# 453_mic.net
KiCad netlist of a schematic drawn in EAGLE
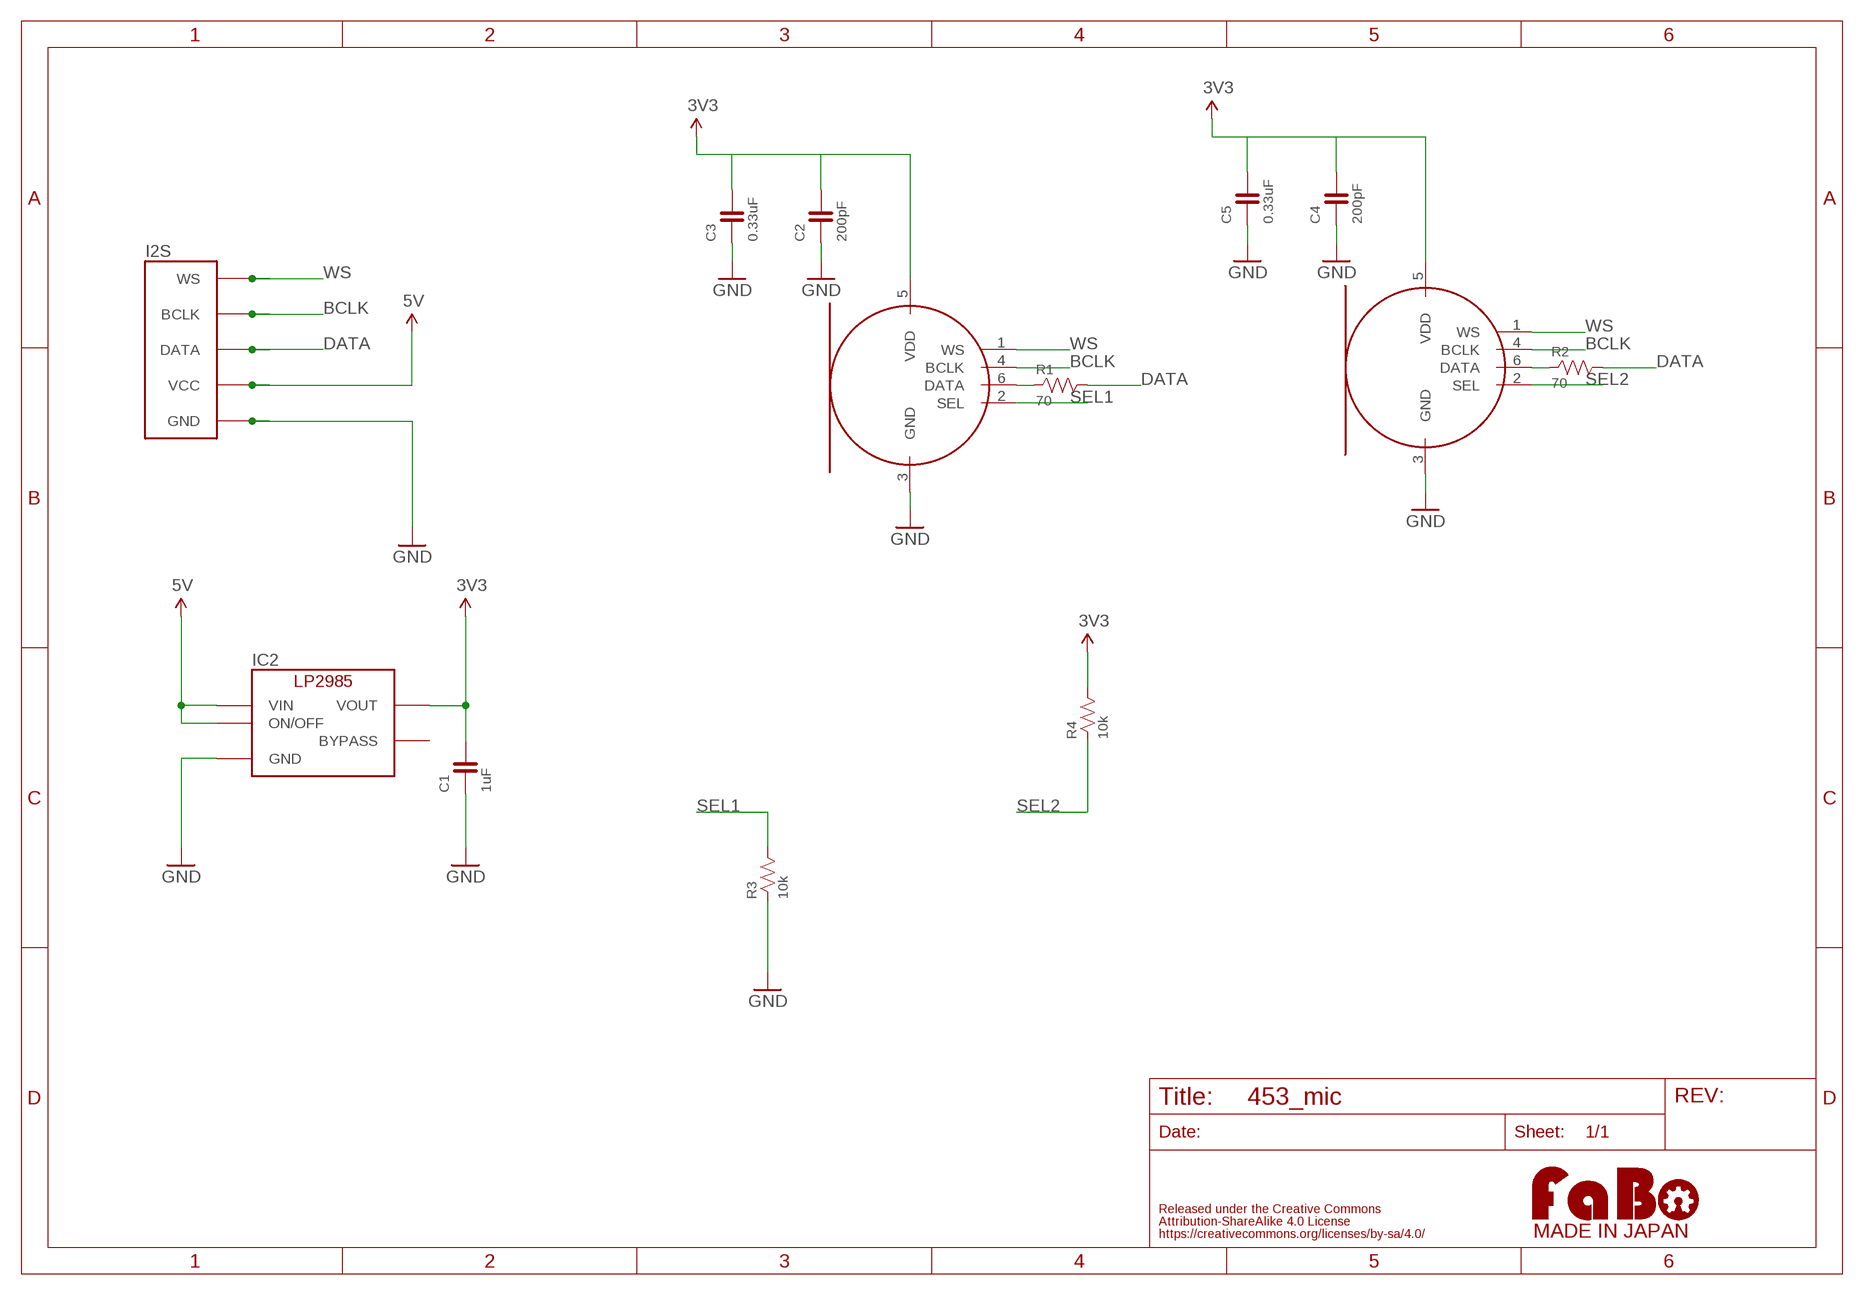
[diagram p0: schematic, sheet 1]

(export (version "E")
  (design (tool "Eeschema 10.0.6"))
  (components
    (comp (ref "C1")
      (value "1uF")
      (footprint "eagle-import:0603")
      (libsource (lib "eagle-import") (part "CAPACITOR-0603"))
    )
    (comp (ref "C2")
      (value "200pF")
      (footprint "eagle-import:0603")
      (libsource (lib "eagle-import") (part "CAPACITOR-0603"))
    )
    (comp (ref "C3")
      (value "0.33uF")
      (footprint "eagle-import:0603")
      (libsource (lib "eagle-import") (part "CAPACITOR-0603"))
    )
    (comp (ref "C4")
      (value "200pF")
      (footprint "eagle-import:0603")
      (libsource (lib "eagle-import") (part "CAPACITOR-0603"))
    )
    (comp (ref "C5")
      (value "0.33uF")
      (footprint "eagle-import:0603")
      (libsource (lib "eagle-import") (part "CAPACITOR-0603"))
    )
    (comp (ref "I2S")
      (value "FABO_BRICK_I2SLONG")
      (footprint "eagle-import:FABO_BRICK_I2S_S05B-PASK-2_LONG")
      (libsource (lib "eagle-import") (part "FABO_BRICK_I2SLONG"))
    )
    (comp (ref "IC2")
      (value "LP2985-33DBV")
      (footprint "eagle-import:SOT-23-5")
      (libsource (lib "eagle-import") (part "LP2985-33DBV"))
    )
    (comp (ref "MIC1")
      (value "KW-SPH0645")
      (footprint "eagle-import:KNOWLES-SPH0645")
      (libsource (lib "eagle-import") (part "KW-SPH0645"))
    )
    (comp (ref "MIC2")
      (value "KW-SPH0645")
      (footprint "eagle-import:KNOWLES-SPH0645")
      (libsource (lib "eagle-import") (part "KW-SPH0645"))
    )
    (comp (ref "R1")
      (value "70")
      (footprint "eagle-import:0603")
      (libsource (lib "eagle-import") (part "RESISTOR-0603"))
    )
    (comp (ref "R2")
      (value "70")
      (footprint "eagle-import:0603")
      (libsource (lib "eagle-import") (part "RESISTOR-0603"))
    )
    (comp (ref "R3")
      (value "10k")
      (footprint "eagle-import:0603")
      (libsource (lib "eagle-import") (part "RESISTOR-0603"))
    )
    (comp (ref "R4")
      (value "10k")
      (footprint "eagle-import:0603")
      (libsource (lib "eagle-import") (part "RESISTOR-0603"))
    )
    (comp (ref "U$3")
      (value "LOGO_FABO-M_BOTTOM")
      (footprint "eagle-import:LOGO_FABO_MS_BOTTOM")
      (libsource (lib "eagle-import") (part "LOGO_FABO-M_BOTTOM"))
    )
  )
  (nets
    (net (code "1") (name "/BCLK") (class "Default")
      (node (ref "I2S") (pin "BCLK") (pinfunction "BCLK_BCLK") (pintype "bidirectional"))
      (node (ref "MIC1") (pin "4") (pinfunction "BCLK_4") (pintype "bidirectional"))
      (node (ref "MIC2") (pin "4") (pinfunction "BCLK_4") (pintype "bidirectional"))
    )
    (net (code "2") (name "/DATA") (class "Default")
      (node (ref "I2S") (pin "DATA") (pinfunction "DATA_DATA") (pintype "bidirectional"))
      (node (ref "R1") (pin "2") (pinfunction "2_2") (pintype "bidirectional"))
      (node (ref "R2") (pin "2") (pinfunction "2_2") (pintype "bidirectional"))
    )
    (net (code "3") (name "/SEL1") (class "Default")
      (node (ref "MIC1") (pin "2") (pinfunction "SEL_2") (pintype "bidirectional"))
      (node (ref "R3") (pin "2") (pinfunction "2_2") (pintype "bidirectional"))
    )
    (net (code "4") (name "/SEL2") (class "Default")
      (node (ref "MIC2") (pin "2") (pinfunction "SEL_2") (pintype "bidirectional"))
      (node (ref "R4") (pin "1") (pinfunction "1_1") (pintype "bidirectional"))
    )
    (net (code "5") (name "/WS") (class "Default")
      (node (ref "I2S") (pin "WS") (pinfunction "WS_WS") (pintype "bidirectional"))
      (node (ref "MIC1") (pin "1") (pinfunction "WS_1") (pintype "bidirectional"))
      (node (ref "MIC2") (pin "1") (pinfunction "WS_1") (pintype "bidirectional"))
    )
    (net (code "6") (name "3V3") (class "Default")
      (node (ref "C1") (pin "2") (pinfunction "2_2") (pintype "passive"))
      (node (ref "C2") (pin "2") (pinfunction "2_2") (pintype "passive"))
      (node (ref "C3") (pin "2") (pinfunction "2_2") (pintype "passive"))
      (node (ref "C4") (pin "2") (pinfunction "2_2") (pintype "passive"))
      (node (ref "C5") (pin "2") (pinfunction "2_2") (pintype "passive"))
      (node (ref "IC2") (pin "5") (pinfunction "VOUT_5") (pintype "output"))
      (node (ref "MIC1") (pin "5") (pinfunction "VDD_5") (pintype "bidirectional"))
      (node (ref "MIC2") (pin "5") (pinfunction "VDD_5") (pintype "bidirectional"))
      (node (ref "R4") (pin "2") (pinfunction "2_2") (pintype "bidirectional"))
    )
    (net (code "7") (name "5V") (class "Default")
      (node (ref "I2S") (pin "VCC") (pinfunction "VCC_VCC") (pintype "bidirectional"))
      (node (ref "IC2") (pin "1") (pinfunction "VIN_1") (pintype "input"))
      (node (ref "IC2") (pin "3") (pinfunction "ON/OFF_3") (pintype "input"))
    )
    (net (code "8") (name "GND") (class "Default")
      (node (ref "C1") (pin "1") (pinfunction "1_1") (pintype "passive"))
      (node (ref "C2") (pin "1") (pinfunction "1_1") (pintype "passive"))
      (node (ref "C3") (pin "1") (pinfunction "1_1") (pintype "passive"))
      (node (ref "C4") (pin "1") (pinfunction "1_1") (pintype "passive"))
      (node (ref "C5") (pin "1") (pinfunction "1_1") (pintype "passive"))
      (node (ref "I2S") (pin "GND") (pinfunction "GND_GND") (pintype "bidirectional"))
      (node (ref "IC2") (pin "2") (pinfunction "GND_2") (pintype "power_in"))
      (node (ref "MIC1") (pin "3") (pinfunction "GND_3") (pintype "bidirectional"))
      (node (ref "MIC2") (pin "3") (pinfunction "GND_3") (pintype "bidirectional"))
      (node (ref "R3") (pin "1") (pinfunction "1_1") (pintype "bidirectional"))
    )
    (net (code "9") (name "Net-(MIC1-DATA)") (class "Default")
      (node (ref "MIC1") (pin "6") (pinfunction "DATA_6") (pintype "bidirectional"))
      (node (ref "R1") (pin "1") (pinfunction "1_1") (pintype "bidirectional"))
    )
    (net (code "10") (name "Net-(MIC2-DATA)") (class "Default")
      (node (ref "MIC2") (pin "6") (pinfunction "DATA_6") (pintype "bidirectional"))
      (node (ref "R2") (pin "1") (pinfunction "1_1") (pintype "bidirectional"))
    )
    (net (code "11") (name "unconnected-(IC2-BYPASS-Pad4)") (class "Default")
      (node (ref "IC2") (pin "4") (pinfunction "BYPASS_4") (pintype "bidirectional"))
    )
  )
)
